# reloj6.net
KiCad netlist of a schematic drawn in EAGLE
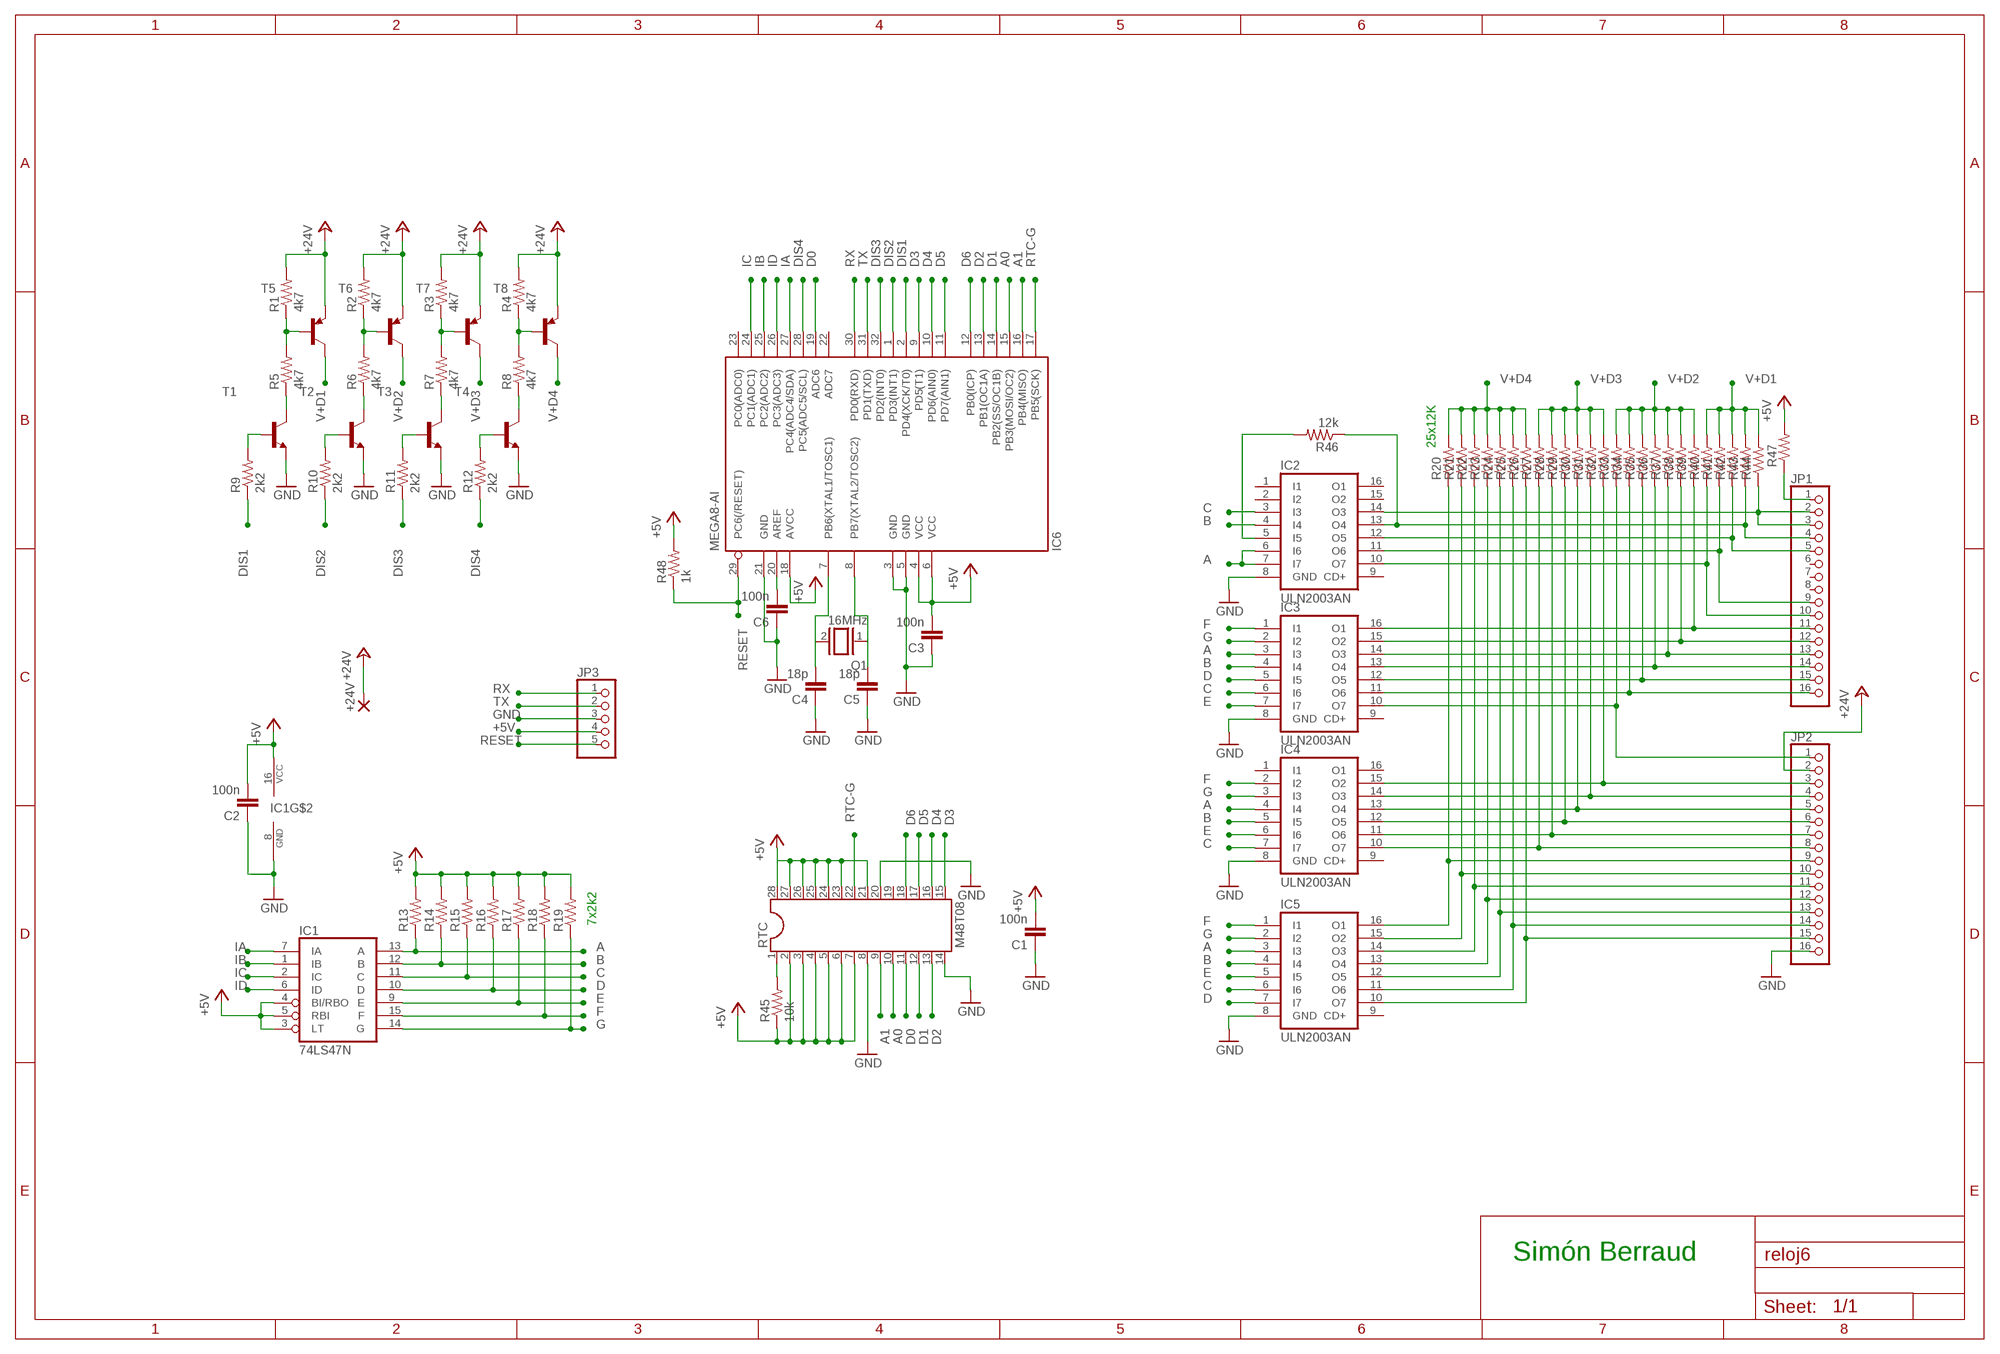
[diagram p0: schematic, sheet 1]

(export (version "E")
  (design (tool "Eeschema 10.0.6"))
  (components
    (comp (ref "+24V")
      (value "2,54/0,8")
      (footprint "eagle-import:2,54_0,8")
      (libsource (lib "eagle-import") (part "2,54/0,8"))
    )
    (comp (ref "C1")
      (value "100n")
      (footprint "eagle-import:C025-025X050")
      (libsource (lib "eagle-import") (part "C-EU025-025X050"))
    )
    (comp (ref "C2")
      (value "100n")
      (footprint "eagle-import:C025-025X050")
      (libsource (lib "eagle-import") (part "C-EU025-025X050"))
    )
    (comp (ref "C3")
      (value "100n")
      (footprint "eagle-import:C025-025X050")
      (libsource (lib "eagle-import") (part "C-EU025-025X050"))
    )
    (comp (ref "C4")
      (value "18p")
      (footprint "eagle-import:C0805K")
      (libsource (lib "eagle-import") (part "resistor_C-EUC0805K"))
    )
    (comp (ref "C5")
      (value "18p")
      (footprint "eagle-import:C0805K")
      (libsource (lib "eagle-import") (part "resistor_C-EUC0805K"))
    )
    (comp (ref "C6")
      (value "100n")
      (footprint "eagle-import:C0805K")
      (libsource (lib "eagle-import") (part "resistor_C-EUC0805K"))
    )
    (comp (ref "IC1")
      (value "74LS47N")
      (footprint "eagle-import:DIL16")
      (libsource (lib "eagle-import") (part "7447NLS"))
    )
    (comp (ref "IC2")
      (value "ULN2003AN")
      (footprint "eagle-import:DIL16")
      (libsource (lib "eagle-import") (part "ULN2003AN"))
    )
    (comp (ref "IC3")
      (value "ULN2003AN")
      (footprint "eagle-import:DIL16")
      (libsource (lib "eagle-import") (part "ULN2003AN"))
    )
    (comp (ref "IC4")
      (value "ULN2003AN")
      (footprint "eagle-import:DIL16")
      (libsource (lib "eagle-import") (part "ULN2003AN"))
    )
    (comp (ref "IC5")
      (value "ULN2003AN")
      (footprint "eagle-import:DIL16")
      (libsource (lib "eagle-import") (part "ULN2003AN"))
    )
    (comp (ref "IC6")
      (value "MEGA8-AI")
      (footprint "eagle-import:TQFP32-08")
      (fields (field (name "MPN") "ATMEGA8-16AU"))
      (libsource (lib "eagle-import") (part "MEGA8-AI"))
    )
    (comp (ref "JP1")
      (value "PINHD-1X16")
      (footprint "eagle-import:1X16")
      (libsource (lib "eagle-import") (part "PINHD-1X16"))
    )
    (comp (ref "JP2")
      (value "PINHD-1X16")
      (footprint "eagle-import:1X16")
      (libsource (lib "eagle-import") (part "PINHD-1X16"))
    )
    (comp (ref "JP3")
      (value "PINHD-1X5")
      (footprint "eagle-import:1X05")
      (libsource (lib "eagle-import") (part "PINHD-1X5"))
    )
    (comp (ref "Q1")
      (value "16MHz")
      (footprint "eagle-import:QS")
      (libsource (lib "eagle-import") (part "XTAL/S"))
    )
    (comp (ref "R1")
      (value "4k7")
      (footprint "eagle-import:0207_7")
      (libsource (lib "eagle-import") (part "R-US_0207/7"))
    )
    (comp (ref "R2")
      (value "4k7")
      (footprint "eagle-import:0207_7")
      (libsource (lib "eagle-import") (part "R-US_0207/7"))
    )
    (comp (ref "R3")
      (value "4k7")
      (footprint "eagle-import:0207_7")
      (libsource (lib "eagle-import") (part "R-US_0207/7"))
    )
    (comp (ref "R4")
      (value "4k7")
      (footprint "eagle-import:0207_7")
      (libsource (lib "eagle-import") (part "R-US_0207/7"))
    )
    (comp (ref "R5")
      (value "4k7")
      (footprint "eagle-import:0207_7")
      (libsource (lib "eagle-import") (part "R-US_0207/7"))
    )
    (comp (ref "R6")
      (value "4k7")
      (footprint "eagle-import:0207_7")
      (libsource (lib "eagle-import") (part "R-US_0207/7"))
    )
    (comp (ref "R7")
      (value "4k7")
      (footprint "eagle-import:0207_7")
      (libsource (lib "eagle-import") (part "R-US_0207/7"))
    )
    (comp (ref "R8")
      (value "4k7")
      (footprint "eagle-import:0207_7")
      (libsource (lib "eagle-import") (part "R-US_0207/7"))
    )
    (comp (ref "R9")
      (value "2k2")
      (footprint "eagle-import:0207_7")
      (libsource (lib "eagle-import") (part "R-US_0207/7"))
    )
    (comp (ref "R10")
      (value "2k2")
      (footprint "eagle-import:0207_7")
      (libsource (lib "eagle-import") (part "R-US_0207/7"))
    )
    (comp (ref "R11")
      (value "2k2")
      (footprint "eagle-import:0207_7")
      (libsource (lib "eagle-import") (part "R-US_0207/7"))
    )
    (comp (ref "R12")
      (value "2k2")
      (footprint "eagle-import:0207_7")
      (libsource (lib "eagle-import") (part "R-US_0207/7"))
    )
    (comp (ref "R13")
      (value "R-US_0207/7")
      (footprint "eagle-import:0207_7")
      (libsource (lib "eagle-import") (part "R-US_0207/7"))
    )
    (comp (ref "R14")
      (value "R-US_0207/7")
      (footprint "eagle-import:0207_7")
      (libsource (lib "eagle-import") (part "R-US_0207/7"))
    )
    (comp (ref "R15")
      (value "R-US_0207/7")
      (footprint "eagle-import:0207_7")
      (libsource (lib "eagle-import") (part "R-US_0207/7"))
    )
    (comp (ref "R16")
      (value "R-US_0207/7")
      (footprint "eagle-import:0207_7")
      (libsource (lib "eagle-import") (part "R-US_0207/7"))
    )
    (comp (ref "R17")
      (value "R-US_0207/7")
      (footprint "eagle-import:0207_7")
      (libsource (lib "eagle-import") (part "R-US_0207/7"))
    )
    (comp (ref "R18")
      (value "R-US_0207/7")
      (footprint "eagle-import:0207_7")
      (libsource (lib "eagle-import") (part "R-US_0207/7"))
    )
    (comp (ref "R19")
      (value "R-US_0207/7")
      (footprint "eagle-import:0207_7")
      (libsource (lib "eagle-import") (part "R-US_0207/7"))
    )
    (comp (ref "R20")
      (value "R-US_0207/7")
      (footprint "eagle-import:0207_7")
      (libsource (lib "eagle-import") (part "R-US_0207/7"))
    )
    (comp (ref "R21")
      (value "R-US_0207/7")
      (footprint "eagle-import:0207_7")
      (libsource (lib "eagle-import") (part "R-US_0207/7"))
    )
    (comp (ref "R22")
      (value "R-US_0207/7")
      (footprint "eagle-import:0207_7")
      (libsource (lib "eagle-import") (part "R-US_0207/7"))
    )
    (comp (ref "R23")
      (value "R-US_0207/7")
      (footprint "eagle-import:0207_7")
      (libsource (lib "eagle-import") (part "R-US_0207/7"))
    )
    (comp (ref "R24")
      (value "R-US_0207/7")
      (footprint "eagle-import:0207_7")
      (libsource (lib "eagle-import") (part "R-US_0207/7"))
    )
    (comp (ref "R25")
      (value "R-US_0207/7")
      (footprint "eagle-import:0207_7")
      (libsource (lib "eagle-import") (part "R-US_0207/7"))
    )
    (comp (ref "R26")
      (value "R-US_0207/7")
      (footprint "eagle-import:0207_7")
      (libsource (lib "eagle-import") (part "R-US_0207/7"))
    )
    (comp (ref "R27")
      (value "R-US_0207/7")
      (footprint "eagle-import:0207_7")
      (libsource (lib "eagle-import") (part "R-US_0207/7"))
    )
    (comp (ref "R28")
      (value "R-US_0207/7")
      (footprint "eagle-import:0207_7")
      (libsource (lib "eagle-import") (part "R-US_0207/7"))
    )
    (comp (ref "R29")
      (value "R-US_0207/7")
      (footprint "eagle-import:0207_7")
      (libsource (lib "eagle-import") (part "R-US_0207/7"))
    )
    (comp (ref "R30")
      (value "R-US_0207/7")
      (footprint "eagle-import:0207_7")
      (libsource (lib "eagle-import") (part "R-US_0207/7"))
    )
    (comp (ref "R31")
      (value "R-US_0207/7")
      (footprint "eagle-import:0207_7")
      (libsource (lib "eagle-import") (part "R-US_0207/7"))
    )
    (comp (ref "R32")
      (value "R-US_0207/7")
      (footprint "eagle-import:0207_7")
      (libsource (lib "eagle-import") (part "R-US_0207/7"))
    )
    (comp (ref "R33")
      (value "R-US_0207/7")
      (footprint "eagle-import:0207_7")
      (libsource (lib "eagle-import") (part "R-US_0207/7"))
    )
    (comp (ref "R34")
      (value "R-US_0207/7")
      (footprint "eagle-import:0207_7")
      (libsource (lib "eagle-import") (part "R-US_0207/7"))
    )
    (comp (ref "R35")
      (value "R-US_0207/7")
      (footprint "eagle-import:0207_7")
      (libsource (lib "eagle-import") (part "R-US_0207/7"))
    )
    (comp (ref "R36")
      (value "R-US_0207/7")
      (footprint "eagle-import:0207_7")
      (libsource (lib "eagle-import") (part "R-US_0207/7"))
    )
    (comp (ref "R37")
      (value "R-US_0207/7")
      (footprint "eagle-import:0207_7")
      (libsource (lib "eagle-import") (part "R-US_0207/7"))
    )
    (comp (ref "R38")
      (value "R-US_0207/7")
      (footprint "eagle-import:0207_7")
      (libsource (lib "eagle-import") (part "R-US_0207/7"))
    )
    (comp (ref "R39")
      (value "R-US_0207/7")
      (footprint "eagle-import:0207_7")
      (libsource (lib "eagle-import") (part "R-US_0207/7"))
    )
    (comp (ref "R40")
      (value "R-US_0207/7")
      (footprint "eagle-import:0207_7")
      (libsource (lib "eagle-import") (part "R-US_0207/7"))
    )
    (comp (ref "R41")
      (value "R-US_0207/7")
      (footprint "eagle-import:0207_7")
      (libsource (lib "eagle-import") (part "R-US_0207/7"))
    )
    (comp (ref "R42")
      (value "R-US_0207/7")
      (footprint "eagle-import:0207_7")
      (libsource (lib "eagle-import") (part "R-US_0207/7"))
    )
    (comp (ref "R43")
      (value "R-US_0207/7")
      (footprint "eagle-import:0207_7")
      (libsource (lib "eagle-import") (part "R-US_0207/7"))
    )
    (comp (ref "R44")
      (value "R-US_0207/7")
      (footprint "eagle-import:0207_7")
      (libsource (lib "eagle-import") (part "R-US_0207/7"))
    )
    (comp (ref "R45")
      (value "10k")
      (footprint "eagle-import:0207_7")
      (libsource (lib "eagle-import") (part "R-US_0207/7"))
    )
    (comp (ref "R46")
      (value "12k")
      (footprint "eagle-import:0207_7")
      (libsource (lib "eagle-import") (part "R-US_0207/7"))
    )
    (comp (ref "R47")
      (value "R-US_0411/12")
      (footprint "eagle-import:0411_12")
      (libsource (lib "eagle-import") (part "R-US_0411/12"))
    )
    (comp (ref "R48")
      (value "1k")
      (footprint "eagle-import:R1206")
      (libsource (lib "eagle-import") (part "R-US_R1206"))
    )
    (comp (ref "RTC")
      (value "M48T08")
      (footprint "eagle-import:DIL28-6")
      (libsource (lib "eagle-import") (part "DIL28"))
    )
    (comp (ref "T1")
      (value "BC169-NPN-TO92-ECB")
      (footprint "eagle-import:TO92-ECB")
      (libsource (lib "eagle-import") (part "-NPN-TO92-ECBBC169"))
    )
    (comp (ref "T2")
      (value "BC169-NPN-TO92-ECB")
      (footprint "eagle-import:TO92-ECB")
      (libsource (lib "eagle-import") (part "-NPN-TO92-ECBBC169"))
    )
    (comp (ref "T3")
      (value "BC169-NPN-TO92-ECB")
      (footprint "eagle-import:TO92-ECB")
      (libsource (lib "eagle-import") (part "-NPN-TO92-ECBBC169"))
    )
    (comp (ref "T4")
      (value "BC169-NPN-TO92-ECB")
      (footprint "eagle-import:TO92-ECB")
      (libsource (lib "eagle-import") (part "-NPN-TO92-ECBBC169"))
    )
    (comp (ref "T5")
      (value "-PNP-TO92-ECB")
      (footprint "eagle-import:TO92-ECB")
      (libsource (lib "eagle-import") (part "-PNP-TO92-ECB"))
    )
    (comp (ref "T6")
      (value "-PNP-TO92-ECB")
      (footprint "eagle-import:TO92-ECB")
      (libsource (lib "eagle-import") (part "-PNP-TO92-ECB"))
    )
    (comp (ref "T7")
      (value "-PNP-TO92-ECB")
      (footprint "eagle-import:TO92-ECB")
      (libsource (lib "eagle-import") (part "-PNP-TO92-ECB"))
    )
    (comp (ref "T8")
      (value "-PNP-TO92-ECB")
      (footprint "eagle-import:TO92-ECB")
      (libsource (lib "eagle-import") (part "-PNP-TO92-ECB"))
    )
  )
  (nets
    (net (code "1") (name "+5V") (class "Default")
      (node (ref "C1") (pin "2") (pinfunction "2_2") (pintype "passive"))
      (node (ref "C2") (pin "2") (pinfunction "2_2") (pintype "passive"))
      (node (ref "C3") (pin "2") (pinfunction "2_2") (pintype "passive"))
      (node (ref "IC1") (pin "16") (pinfunction "VCC_16") (pintype "power_in"))
      (node (ref "IC1") (pin "3") (pinfunction "LT_3") (pintype "input"))
      (node (ref "IC1") (pin "4") (pinfunction "BI/RBO_4") (pintype "input"))
      (node (ref "IC1") (pin "5") (pinfunction "RBI_5") (pintype "input"))
      (node (ref "IC6") (pin "18") (pinfunction "AVCC_18") (pintype "power_in"))
      (node (ref "IC6") (pin "4") (pinfunction "VCC_4") (pintype "power_in"))
      (node (ref "IC6") (pin "6") (pinfunction "VCC_6") (pintype "power_in"))
      (node (ref "JP3") (pin "4") (pinfunction "4_4") (pintype "passive"))
      (node (ref "R13") (pin "2") (pinfunction "2_2") (pintype "passive"))
      (node (ref "R14") (pin "2") (pinfunction "2_2") (pintype "passive"))
      (node (ref "R15") (pin "2") (pinfunction "2_2") (pintype "passive"))
      (node (ref "R16") (pin "2") (pinfunction "2_2") (pintype "passive"))
      (node (ref "R17") (pin "2") (pinfunction "2_2") (pintype "passive"))
      (node (ref "R18") (pin "2") (pinfunction "2_2") (pintype "passive"))
      (node (ref "R19") (pin "2") (pinfunction "2_2") (pintype "passive"))
      (node (ref "R45") (pin "1") (pinfunction "1_1") (pintype "passive"))
      (node (ref "R47") (pin "2") (pinfunction "2_2") (pintype "passive"))
      (node (ref "R48") (pin "2") (pinfunction "2_2") (pintype "passive"))
      (node (ref "RTC") (pin "2") (pinfunction "2_2") (pintype "passive"))
      (node (ref "RTC") (pin "21") (pinfunction "21_21") (pintype "passive"))
      (node (ref "RTC") (pin "23") (pinfunction "23_23") (pintype "passive"))
      (node (ref "RTC") (pin "24") (pinfunction "24_24") (pintype "passive"))
      (node (ref "RTC") (pin "25") (pinfunction "25_25") (pintype "passive"))
      (node (ref "RTC") (pin "26") (pinfunction "26_26") (pintype "passive"))
      (node (ref "RTC") (pin "27") (pinfunction "27_27") (pintype "passive"))
      (node (ref "RTC") (pin "28") (pinfunction "28_28") (pintype "passive"))
      (node (ref "RTC") (pin "3") (pinfunction "3_3") (pintype "passive"))
      (node (ref "RTC") (pin "4") (pinfunction "4_4") (pintype "passive"))
      (node (ref "RTC") (pin "5") (pinfunction "5_5") (pintype "passive"))
      (node (ref "RTC") (pin "6") (pinfunction "6_6") (pintype "passive"))
      (node (ref "RTC") (pin "7") (pinfunction "7_7") (pintype "passive"))
    )
    (net (code "2") (name "+24V") (class "Default")
      (node (ref "+24V") (pin "1") (pinfunction "P_1") (pintype "passive"))
      (node (ref "JP2") (pin "2") (pinfunction "2_2") (pintype "passive"))
      (node (ref "R1") (pin "2") (pinfunction "2_2") (pintype "passive"))
      (node (ref "R2") (pin "2") (pinfunction "2_2") (pintype "passive"))
      (node (ref "R3") (pin "2") (pinfunction "2_2") (pintype "passive"))
      (node (ref "R4") (pin "2") (pinfunction "2_2") (pintype "passive"))
      (node (ref "T5") (pin "E") (pinfunction "E_E") (pintype "passive"))
      (node (ref "T6") (pin "E") (pinfunction "E_E") (pintype "passive"))
      (node (ref "T7") (pin "E") (pinfunction "E_E") (pintype "passive"))
      (node (ref "T8") (pin "E") (pinfunction "E_E") (pintype "passive"))
    )
    (net (code "3") (name "/A") (class "Default")
      (node (ref "IC1") (pin "13") (pinfunction "A_13") (pintype "output"))
      (node (ref "IC2") (pin "6") (pinfunction "I6_6") (pintype "input"))
      (node (ref "IC2") (pin "7") (pinfunction "I7_7") (pintype "input"))
      (node (ref "IC3") (pin "3") (pinfunction "I3_3") (pintype "input"))
      (node (ref "IC4") (pin "4") (pinfunction "I4_4") (pintype "input"))
      (node (ref "IC5") (pin "3") (pinfunction "I3_3") (pintype "input"))
      (node (ref "R13") (pin "1") (pinfunction "1_1") (pintype "passive"))
    )
    (net (code "4") (name "/A0") (class "Default")
      (node (ref "IC6") (pin "15") (pinfunction "PB3(MOSI/OC2)_15") (pintype "bidirectional"))
      (node (ref "RTC") (pin "10") (pinfunction "10_10") (pintype "passive"))
    )
    (net (code "5") (name "/A1") (class "Default")
      (node (ref "IC6") (pin "16") (pinfunction "PB4(MISO)_16") (pintype "bidirectional"))
      (node (ref "RTC") (pin "9") (pinfunction "9_9") (pintype "passive"))
    )
    (net (code "6") (name "/B") (class "Default")
      (node (ref "IC1") (pin "12") (pinfunction "B_12") (pintype "output"))
      (node (ref "IC2") (pin "4") (pinfunction "I4_4") (pintype "input"))
      (node (ref "IC3") (pin "4") (pinfunction "I4_4") (pintype "input"))
      (node (ref "IC4") (pin "5") (pinfunction "I5_5") (pintype "input"))
      (node (ref "IC5") (pin "4") (pinfunction "I4_4") (pintype "input"))
      (node (ref "R14") (pin "1") (pinfunction "1_1") (pintype "passive"))
    )
    (net (code "7") (name "/C") (class "Default")
      (node (ref "IC1") (pin "11") (pinfunction "C_11") (pintype "output"))
      (node (ref "IC2") (pin "3") (pinfunction "I3_3") (pintype "input"))
      (node (ref "IC3") (pin "6") (pinfunction "I6_6") (pintype "input"))
      (node (ref "IC4") (pin "7") (pinfunction "I7_7") (pintype "input"))
      (node (ref "IC5") (pin "6") (pinfunction "I6_6") (pintype "input"))
      (node (ref "R15") (pin "1") (pinfunction "1_1") (pintype "passive"))
    )
    (net (code "8") (name "/D") (class "Default")
      (node (ref "IC1") (pin "10") (pinfunction "D_10") (pintype "output"))
      (node (ref "IC3") (pin "5") (pinfunction "I5_5") (pintype "input"))
      (node (ref "IC5") (pin "7") (pinfunction "I7_7") (pintype "input"))
      (node (ref "R16") (pin "1") (pinfunction "1_1") (pintype "passive"))
    )
    (net (code "9") (name "/D0") (class "Default")
      (node (ref "IC6") (pin "19") (pinfunction "ADC6_19") (pintype "bidirectional"))
      (node (ref "RTC") (pin "11") (pinfunction "11_11") (pintype "passive"))
    )
    (net (code "10") (name "/D1") (class "Default")
      (node (ref "IC6") (pin "14") (pinfunction "PB2(SS/OC1B)_14") (pintype "bidirectional"))
      (node (ref "RTC") (pin "12") (pinfunction "12_12") (pintype "passive"))
    )
    (net (code "11") (name "/D2") (class "Default")
      (node (ref "IC6") (pin "13") (pinfunction "PB1(OC1A)_13") (pintype "bidirectional"))
      (node (ref "RTC") (pin "13") (pinfunction "13_13") (pintype "passive"))
    )
    (net (code "12") (name "/D3") (class "Default")
      (node (ref "IC6") (pin "9") (pinfunction "PD5(T1)_9") (pintype "bidirectional"))
      (node (ref "RTC") (pin "15") (pinfunction "15_15") (pintype "passive"))
    )
    (net (code "13") (name "/D4") (class "Default")
      (node (ref "IC6") (pin "10") (pinfunction "PD6(AIN0)_10") (pintype "bidirectional"))
      (node (ref "RTC") (pin "16") (pinfunction "16_16") (pintype "passive"))
    )
    (net (code "14") (name "/D5") (class "Default")
      (node (ref "IC6") (pin "11") (pinfunction "PD7(AIN1)_11") (pintype "bidirectional"))
      (node (ref "RTC") (pin "17") (pinfunction "17_17") (pintype "passive"))
    )
    (net (code "15") (name "/D6") (class "Default")
      (node (ref "IC6") (pin "12") (pinfunction "PB0(ICP)_12") (pintype "bidirectional"))
      (node (ref "RTC") (pin "18") (pinfunction "18_18") (pintype "passive"))
    )
    (net (code "16") (name "/DIS1") (class "Default")
      (node (ref "IC6") (pin "2") (pinfunction "PD4(XCK/T0)_2") (pintype "bidirectional"))
      (node (ref "R9") (pin "1") (pinfunction "1_1") (pintype "passive"))
    )
    (net (code "17") (name "/DIS2") (class "Default")
      (node (ref "IC6") (pin "1") (pinfunction "PD3(INT1)_1") (pintype "bidirectional"))
      (node (ref "R10") (pin "1") (pinfunction "1_1") (pintype "passive"))
    )
    (net (code "18") (name "/DIS3") (class "Default")
      (node (ref "IC6") (pin "32") (pinfunction "PD2(INT0)_32") (pintype "bidirectional"))
      (node (ref "R11") (pin "1") (pinfunction "1_1") (pintype "passive"))
    )
    (net (code "19") (name "/DIS4") (class "Default")
      (node (ref "IC6") (pin "28") (pinfunction "PC5(ADC5/SCL)_28") (pintype "bidirectional"))
      (node (ref "R12") (pin "1") (pinfunction "1_1") (pintype "passive"))
    )
    (net (code "20") (name "/E") (class "Default")
      (node (ref "IC1") (pin "9") (pinfunction "E_9") (pintype "output"))
      (node (ref "IC3") (pin "7") (pinfunction "I7_7") (pintype "input"))
      (node (ref "IC4") (pin "6") (pinfunction "I6_6") (pintype "input"))
      (node (ref "IC5") (pin "5") (pinfunction "I5_5") (pintype "input"))
      (node (ref "R17") (pin "1") (pinfunction "1_1") (pintype "passive"))
    )
    (net (code "21") (name "/F") (class "Default")
      (node (ref "IC1") (pin "15") (pinfunction "F_15") (pintype "output"))
      (node (ref "IC3") (pin "1") (pinfunction "I1_1") (pintype "input"))
      (node (ref "IC4") (pin "2") (pinfunction "I2_2") (pintype "input"))
      (node (ref "IC5") (pin "1") (pinfunction "I1_1") (pintype "input"))
      (node (ref "R18") (pin "1") (pinfunction "1_1") (pintype "passive"))
    )
    (net (code "22") (name "/G") (class "Default")
      (node (ref "IC1") (pin "14") (pinfunction "G_14") (pintype "output"))
      (node (ref "IC3") (pin "2") (pinfunction "I2_2") (pintype "input"))
      (node (ref "IC4") (pin "3") (pinfunction "I3_3") (pintype "input"))
      (node (ref "IC5") (pin "2") (pinfunction "I2_2") (pintype "input"))
      (node (ref "R19") (pin "1") (pinfunction "1_1") (pintype "passive"))
    )
    (net (code "23") (name "/IA") (class "Default")
      (node (ref "IC1") (pin "7") (pinfunction "IA_7") (pintype "input"))
      (node (ref "IC6") (pin "27") (pinfunction "PC4(ADC4/SDA)_27") (pintype "bidirectional"))
    )
    (net (code "24") (name "/IB") (class "Default")
      (node (ref "IC1") (pin "1") (pinfunction "IB_1") (pintype "input"))
      (node (ref "IC6") (pin "25") (pinfunction "PC2(ADC2)_25") (pintype "bidirectional"))
    )
    (net (code "25") (name "/IC") (class "Default")
      (node (ref "IC1") (pin "2") (pinfunction "IC_2") (pintype "input"))
      (node (ref "IC6") (pin "24") (pinfunction "PC1(ADC1)_24") (pintype "bidirectional"))
    )
    (net (code "26") (name "/ID") (class "Default")
      (node (ref "IC1") (pin "6") (pinfunction "ID_6") (pintype "input"))
      (node (ref "IC6") (pin "26") (pinfunction "PC3(ADC3)_26") (pintype "bidirectional"))
    )
    (net (code "27") (name "/RESET") (class "Default")
      (node (ref "IC6") (pin "29") (pinfunction "PC6(/RESET)_29") (pintype "bidirectional"))
      (node (ref "JP3") (pin "5") (pinfunction "5_5") (pintype "passive"))
      (node (ref "R48") (pin "1") (pinfunction "1_1") (pintype "passive"))
    )
    (net (code "28") (name "/RTC-G") (class "Default")
      (node (ref "IC6") (pin "17") (pinfunction "PB5(SCK)_17") (pintype "bidirectional"))
      (node (ref "RTC") (pin "22") (pinfunction "22_22") (pintype "passive"))
    )
    (net (code "29") (name "/RX") (class "Default")
      (node (ref "IC6") (pin "30") (pinfunction "PD0(RXD)_30") (pintype "bidirectional"))
      (node (ref "JP3") (pin "1") (pinfunction "1_1") (pintype "passive"))
    )
    (net (code "30") (name "/TX") (class "Default")
      (node (ref "IC6") (pin "31") (pinfunction "PD1(TXD)_31") (pintype "bidirectional"))
      (node (ref "JP3") (pin "2") (pinfunction "2_2") (pintype "passive"))
    )
    (net (code "31") (name "/V+D1") (class "Default")
      (node (ref "R40") (pin "2") (pinfunction "2_2") (pintype "passive"))
      (node (ref "R41") (pin "2") (pinfunction "2_2") (pintype "passive"))
      (node (ref "R42") (pin "2") (pinfunction "2_2") (pintype "passive"))
      (node (ref "R43") (pin "2") (pinfunction "2_2") (pintype "passive"))
      (node (ref "R44") (pin "2") (pinfunction "2_2") (pintype "passive"))
      (node (ref "T5") (pin "C") (pinfunction "C_C") (pintype "passive"))
    )
    (net (code "32") (name "/V+D2") (class "Default")
      (node (ref "R33") (pin "2") (pinfunction "2_2") (pintype "passive"))
      (node (ref "R34") (pin "2") (pinfunction "2_2") (pintype "passive"))
      (node (ref "R35") (pin "2") (pinfunction "2_2") (pintype "passive"))
      (node (ref "R36") (pin "2") (pinfunction "2_2") (pintype "passive"))
      (node (ref "R37") (pin "2") (pinfunction "2_2") (pintype "passive"))
      (node (ref "R38") (pin "2") (pinfunction "2_2") (pintype "passive"))
      (node (ref "R39") (pin "2") (pinfunction "2_2") (pintype "passive"))
      (node (ref "T6") (pin "C") (pinfunction "C_C") (pintype "passive"))
    )
    (net (code "33") (name "/V+D3") (class "Default")
      (node (ref "R27") (pin "2") (pinfunction "2_2") (pintype "passive"))
      (node (ref "R28") (pin "2") (pinfunction "2_2") (pintype "passive"))
      (node (ref "R29") (pin "2") (pinfunction "2_2") (pintype "passive"))
      (node (ref "R30") (pin "2") (pinfunction "2_2") (pintype "passive"))
      (node (ref "R31") (pin "2") (pinfunction "2_2") (pintype "passive"))
      (node (ref "R32") (pin "2") (pinfunction "2_2") (pintype "passive"))
      (node (ref "T7") (pin "C") (pinfunction "C_C") (pintype "passive"))
    )
    (net (code "34") (name "/V+D4") (class "Default")
      (node (ref "R20") (pin "2") (pinfunction "2_2") (pintype "passive"))
      (node (ref "R21") (pin "2") (pinfunction "2_2") (pintype "passive"))
      (node (ref "R22") (pin "2") (pinfunction "2_2") (pintype "passive"))
      (node (ref "R23") (pin "2") (pinfunction "2_2") (pintype "passive"))
      (node (ref "R24") (pin "2") (pinfunction "2_2") (pintype "passive"))
      (node (ref "R25") (pin "2") (pinfunction "2_2") (pintype "passive"))
      (node (ref "R26") (pin "2") (pinfunction "2_2") (pintype "passive"))
      (node (ref "T8") (pin "C") (pinfunction "C_C") (pintype "passive"))
    )
    (net (code "35") (name "GND") (class "Default")
      (node (ref "C1") (pin "1") (pinfunction "1_1") (pintype "passive"))
      (node (ref "C2") (pin "1") (pinfunction "1_1") (pintype "passive"))
      (node (ref "C3") (pin "1") (pinfunction "1_1") (pintype "passive"))
      (node (ref "C4") (pin "1") (pinfunction "1_1") (pintype "passive"))
      (node (ref "C5") (pin "1") (pinfunction "1_1") (pintype "passive"))
      (node (ref "C6") (pin "1") (pinfunction "1_1") (pintype "passive"))
      (node (ref "IC1") (pin "8") (pinfunction "GND_8") (pintype "power_in"))
      (node (ref "IC2") (pin "8") (pinfunction "GND_8") (pintype "power_in"))
      (node (ref "IC3") (pin "8") (pinfunction "GND_8") (pintype "power_in"))
      (node (ref "IC4") (pin "8") (pinfunction "GND_8") (pintype "power_in"))
      (node (ref "IC5") (pin "8") (pinfunction "GND_8") (pintype "power_in"))
      (node (ref "IC6") (pin "21") (pinfunction "GND_21") (pintype "power_in"))
      (node (ref "IC6") (pin "3") (pinfunction "GND_3") (pintype "power_in"))
      (node (ref "IC6") (pin "5") (pinfunction "GND_5") (pintype "power_in"))
      (node (ref "JP2") (pin "16") (pinfunction "16_16") (pintype "passive"))
      (node (ref "JP3") (pin "3") (pinfunction "3_3") (pintype "passive"))
      (node (ref "RTC") (pin "14") (pinfunction "14_14") (pintype "passive"))
      (node (ref "RTC") (pin "20") (pinfunction "20_20") (pintype "passive"))
      (node (ref "RTC") (pin "8") (pinfunction "8_8") (pintype "passive"))
      (node (ref "T1") (pin "E") (pinfunction "E_E") (pintype "passive"))
      (node (ref "T2") (pin "E") (pinfunction "E_E") (pintype "passive"))
      (node (ref "T3") (pin "E") (pinfunction "E_E") (pintype "passive"))
      (node (ref "T4") (pin "E") (pinfunction "E_E") (pintype "passive"))
    )
    (net (code "36") (name "Net-(IC2-I5)") (class "Default")
      (node (ref "IC2") (pin "5") (pinfunction "I5_5") (pintype "input"))
      (node (ref "R46") (pin "2") (pinfunction "2_2") (pintype "passive"))
    )
    (net (code "37") (name "Net-(IC2-O3)") (class "Default")
      (node (ref "IC2") (pin "14") (pinfunction "O3_14") (pintype "open_collector"))
      (node (ref "JP1") (pin "2") (pinfunction "2_2") (pintype "passive"))
      (node (ref "JP1") (pin "3") (pinfunction "3_3") (pintype "passive"))
      (node (ref "R44") (pin "1") (pinfunction "1_1") (pintype "passive"))
    )
    (net (code "38") (name "Net-(IC2-O4)") (class "Default")
      (node (ref "IC2") (pin "13") (pinfunction "O4_13") (pintype "open_collector"))
      (node (ref "JP1") (pin "4") (pinfunction "4_4") (pintype "passive"))
      (node (ref "R43") (pin "1") (pinfunction "1_1") (pintype "passive"))
      (node (ref "R46") (pin "1") (pinfunction "1_1") (pintype "passive"))
    )
    (net (code "39") (name "Net-(IC2-O5)") (class "Default")
      (node (ref "IC2") (pin "12") (pinfunction "O5_12") (pintype "open_collector"))
      (node (ref "JP1") (pin "5") (pinfunction "5_5") (pintype "passive"))
      (node (ref "R42") (pin "1") (pinfunction "1_1") (pintype "passive"))
    )
    (net (code "40") (name "Net-(IC2-O6)") (class "Default")
      (node (ref "IC2") (pin "11") (pinfunction "O6_11") (pintype "open_collector"))
      (node (ref "JP1") (pin "9") (pinfunction "9_9") (pintype "passive"))
      (node (ref "R41") (pin "1") (pinfunction "1_1") (pintype "passive"))
    )
    (net (code "41") (name "Net-(IC2-O7)") (class "Default")
      (node (ref "IC2") (pin "10") (pinfunction "O7_10") (pintype "open_collector"))
      (node (ref "JP1") (pin "10") (pinfunction "10_10") (pintype "passive"))
      (node (ref "R40") (pin "1") (pinfunction "1_1") (pintype "passive"))
    )
    (net (code "42") (name "Net-(IC3-O1)") (class "Default")
      (node (ref "IC3") (pin "16") (pinfunction "O1_16") (pintype "open_collector"))
      (node (ref "JP1") (pin "11") (pinfunction "11_11") (pintype "passive"))
      (node (ref "R39") (pin "1") (pinfunction "1_1") (pintype "passive"))
    )
    (net (code "43") (name "Net-(IC3-O2)") (class "Default")
      (node (ref "IC3") (pin "15") (pinfunction "O2_15") (pintype "open_collector"))
      (node (ref "JP1") (pin "12") (pinfunction "12_12") (pintype "passive"))
      (node (ref "R38") (pin "1") (pinfunction "1_1") (pintype "passive"))
    )
    (net (code "44") (name "Net-(IC3-O3)") (class "Default")
      (node (ref "IC3") (pin "14") (pinfunction "O3_14") (pintype "open_collector"))
      (node (ref "JP1") (pin "13") (pinfunction "13_13") (pintype "passive"))
      (node (ref "R37") (pin "1") (pinfunction "1_1") (pintype "passive"))
    )
    (net (code "45") (name "Net-(IC3-O4)") (class "Default")
      (node (ref "IC3") (pin "13") (pinfunction "O4_13") (pintype "open_collector"))
      (node (ref "JP1") (pin "14") (pinfunction "14_14") (pintype "passive"))
      (node (ref "R36") (pin "1") (pinfunction "1_1") (pintype "passive"))
    )
    (net (code "46") (name "Net-(IC3-O5)") (class "Default")
      (node (ref "IC3") (pin "12") (pinfunction "O5_12") (pintype "open_collector"))
      (node (ref "JP1") (pin "15") (pinfunction "15_15") (pintype "passive"))
      (node (ref "R35") (pin "1") (pinfunction "1_1") (pintype "passive"))
    )
    (net (code "47") (name "Net-(IC3-O6)") (class "Default")
      (node (ref "IC3") (pin "11") (pinfunction "O6_11") (pintype "open_collector"))
      (node (ref "JP1") (pin "16") (pinfunction "16_16") (pintype "passive"))
      (node (ref "R34") (pin "1") (pinfunction "1_1") (pintype "passive"))
    )
    (net (code "48") (name "Net-(IC3-O7)") (class "Default")
      (node (ref "IC3") (pin "10") (pinfunction "O7_10") (pintype "open_collector"))
      (node (ref "JP2") (pin "1") (pinfunction "1_1") (pintype "passive"))
      (node (ref "R33") (pin "1") (pinfunction "1_1") (pintype "passive"))
    )
    (net (code "49") (name "Net-(IC4-O2)") (class "Default")
      (node (ref "IC4") (pin "15") (pinfunction "O2_15") (pintype "open_collector"))
      (node (ref "JP2") (pin "3") (pinfunction "3_3") (pintype "passive"))
      (node (ref "R32") (pin "1") (pinfunction "1_1") (pintype "passive"))
    )
    (net (code "50") (name "Net-(IC4-O3)") (class "Default")
      (node (ref "IC4") (pin "14") (pinfunction "O3_14") (pintype "open_collector"))
      (node (ref "JP2") (pin "4") (pinfunction "4_4") (pintype "passive"))
      (node (ref "R31") (pin "1") (pinfunction "1_1") (pintype "passive"))
    )
    (net (code "51") (name "Net-(IC4-O4)") (class "Default")
      (node (ref "IC4") (pin "13") (pinfunction "O4_13") (pintype "open_collector"))
      (node (ref "JP2") (pin "5") (pinfunction "5_5") (pintype "passive"))
      (node (ref "R30") (pin "1") (pinfunction "1_1") (pintype "passive"))
    )
    (net (code "52") (name "Net-(IC4-O5)") (class "Default")
      (node (ref "IC4") (pin "12") (pinfunction "O5_12") (pintype "open_collector"))
      (node (ref "JP2") (pin "6") (pinfunction "6_6") (pintype "passive"))
      (node (ref "R29") (pin "1") (pinfunction "1_1") (pintype "passive"))
    )
    (net (code "53") (name "Net-(IC4-O6)") (class "Default")
      (node (ref "IC4") (pin "11") (pinfunction "O6_11") (pintype "open_collector"))
      (node (ref "JP2") (pin "7") (pinfunction "7_7") (pintype "passive"))
      (node (ref "R28") (pin "1") (pinfunction "1_1") (pintype "passive"))
    )
    (net (code "54") (name "Net-(IC4-O7)") (class "Default")
      (node (ref "IC4") (pin "10") (pinfunction "O7_10") (pintype "open_collector"))
      (node (ref "JP2") (pin "8") (pinfunction "8_8") (pintype "passive"))
      (node (ref "R27") (pin "1") (pinfunction "1_1") (pintype "passive"))
    )
    (net (code "55") (name "Net-(IC5-O1)") (class "Default")
      (node (ref "IC5") (pin "16") (pinfunction "O1_16") (pintype "open_collector"))
      (node (ref "JP2") (pin "9") (pinfunction "9_9") (pintype "passive"))
      (node (ref "R20") (pin "1") (pinfunction "1_1") (pintype "passive"))
    )
    (net (code "56") (name "Net-(IC5-O2)") (class "Default")
      (node (ref "IC5") (pin "15") (pinfunction "O2_15") (pintype "open_collector"))
      (node (ref "JP2") (pin "10") (pinfunction "10_10") (pintype "passive"))
      (node (ref "R21") (pin "1") (pinfunction "1_1") (pintype "passive"))
    )
    (net (code "57") (name "Net-(IC5-O3)") (class "Default")
      (node (ref "IC5") (pin "14") (pinfunction "O3_14") (pintype "open_collector"))
      (node (ref "JP2") (pin "11") (pinfunction "11_11") (pintype "passive"))
      (node (ref "R22") (pin "1") (pinfunction "1_1") (pintype "passive"))
    )
    (net (code "58") (name "Net-(IC5-O4)") (class "Default")
      (node (ref "IC5") (pin "13") (pinfunction "O4_13") (pintype "open_collector"))
      (node (ref "JP2") (pin "12") (pinfunction "12_12") (pintype "passive"))
      (node (ref "R23") (pin "1") (pinfunction "1_1") (pintype "passive"))
    )
    (net (code "59") (name "Net-(IC5-O5)") (class "Default")
      (node (ref "IC5") (pin "12") (pinfunction "O5_12") (pintype "open_collector"))
      (node (ref "JP2") (pin "13") (pinfunction "13_13") (pintype "passive"))
      (node (ref "R24") (pin "1") (pinfunction "1_1") (pintype "passive"))
    )
    (net (code "60") (name "Net-(IC5-O6)") (class "Default")
      (node (ref "IC5") (pin "11") (pinfunction "O6_11") (pintype "open_collector"))
      (node (ref "JP2") (pin "14") (pinfunction "14_14") (pintype "passive"))
      (node (ref "R25") (pin "1") (pinfunction "1_1") (pintype "passive"))
    )
    (net (code "61") (name "Net-(IC5-O7)") (class "Default")
      (node (ref "IC5") (pin "10") (pinfunction "O7_10") (pintype "open_collector"))
      (node (ref "JP2") (pin "15") (pinfunction "15_15") (pintype "passive"))
      (node (ref "R26") (pin "1") (pinfunction "1_1") (pintype "passive"))
    )
    (net (code "62") (name "Net-(IC6-AREF)") (class "Default")
      (node (ref "C6") (pin "2") (pinfunction "2_2") (pintype "passive"))
      (node (ref "IC6") (pin "20") (pinfunction "AREF_20") (pintype "passive"))
    )
    (net (code "63") (name "Net-(IC6-PB6(XTAL1{slash}TOSC1))") (class "Default")
      (node (ref "C4") (pin "2") (pinfunction "2_2") (pintype "passive"))
      (node (ref "IC6") (pin "7") (pinfunction "PB6(XTAL1/TOSC1)_7") (pintype "bidirectional"))
      (node (ref "Q1") (pin "2") (pinfunction "2_2") (pintype "passive"))
    )
    (net (code "64") (name "Net-(IC6-PB7(XTAL2{slash}TOSC2))") (class "Default")
      (node (ref "C5") (pin "2") (pinfunction "2_2") (pintype "passive"))
      (node (ref "IC6") (pin "8") (pinfunction "PB7(XTAL2/TOSC2)_8") (pintype "bidirectional"))
      (node (ref "Q1") (pin "1") (pinfunction "1_1") (pintype "passive"))
    )
    (net (code "65") (name "Net-(JP1-Pad1)") (class "Default")
      (node (ref "JP1") (pin "1") (pinfunction "1_1") (pintype "passive"))
      (node (ref "R47") (pin "1") (pinfunction "1_1") (pintype "passive"))
    )
    (net (code "66") (name "Net-(R1-Pad1)") (class "Default")
      (node (ref "R1") (pin "1") (pinfunction "1_1") (pintype "passive"))
      (node (ref "R5") (pin "2") (pinfunction "2_2") (pintype "passive"))
      (node (ref "T5") (pin "B") (pinfunction "B_B") (pintype "passive"))
    )
    (net (code "67") (name "Net-(R2-Pad1)") (class "Default")
      (node (ref "R2") (pin "1") (pinfunction "1_1") (pintype "passive"))
      (node (ref "R6") (pin "2") (pinfunction "2_2") (pintype "passive"))
      (node (ref "T6") (pin "B") (pinfunction "B_B") (pintype "passive"))
    )
    (net (code "68") (name "Net-(R3-Pad1)") (class "Default")
      (node (ref "R3") (pin "1") (pinfunction "1_1") (pintype "passive"))
      (node (ref "R7") (pin "2") (pinfunction "2_2") (pintype "passive"))
      (node (ref "T7") (pin "B") (pinfunction "B_B") (pintype "passive"))
    )
    (net (code "69") (name "Net-(R4-Pad1)") (class "Default")
      (node (ref "R4") (pin "1") (pinfunction "1_1") (pintype "passive"))
      (node (ref "R8") (pin "2") (pinfunction "2_2") (pintype "passive"))
      (node (ref "T8") (pin "B") (pinfunction "B_B") (pintype "passive"))
    )
    (net (code "70") (name "Net-(R5-Pad1)") (class "Default")
      (node (ref "R5") (pin "1") (pinfunction "1_1") (pintype "passive"))
      (node (ref "T1") (pin "C") (pinfunction "C_C") (pintype "passive"))
    )
    (net (code "71") (name "Net-(R6-Pad1)") (class "Default")
      (node (ref "R6") (pin "1") (pinfunction "1_1") (pintype "passive"))
      (node (ref "T2") (pin "C") (pinfunction "C_C") (pintype "passive"))
    )
    (net (code "72") (name "Net-(R7-Pad1)") (class "Default")
      (node (ref "R7") (pin "1") (pinfunction "1_1") (pintype "passive"))
      (node (ref "T3") (pin "C") (pinfunction "C_C") (pintype "passive"))
    )
    (net (code "73") (name "Net-(R8-Pad1)") (class "Default")
      (node (ref "R8") (pin "1") (pinfunction "1_1") (pintype "passive"))
      (node (ref "T4") (pin "C") (pinfunction "C_C") (pintype "passive"))
    )
    (net (code "74") (name "Net-(R9-Pad2)") (class "Default")
      (node (ref "R9") (pin "2") (pinfunction "2_2") (pintype "passive"))
      (node (ref "T1") (pin "B") (pinfunction "B_B") (pintype "passive"))
    )
    (net (code "75") (name "Net-(R10-Pad2)") (class "Default")
      (node (ref "R10") (pin "2") (pinfunction "2_2") (pintype "passive"))
      (node (ref "T2") (pin "B") (pinfunction "B_B") (pintype "passive"))
    )
    (net (code "76") (name "Net-(R11-Pad2)") (class "Default")
      (node (ref "R11") (pin "2") (pinfunction "2_2") (pintype "passive"))
      (node (ref "T3") (pin "B") (pinfunction "B_B") (pintype "passive"))
    )
    (net (code "77") (name "Net-(R12-Pad2)") (class "Default")
      (node (ref "R12") (pin "2") (pinfunction "2_2") (pintype "passive"))
      (node (ref "T4") (pin "B") (pinfunction "B_B") (pintype "passive"))
    )
    (net (code "78") (name "Net-(R45-Pad2)") (class "Default")
      (node (ref "R45") (pin "2") (pinfunction "2_2") (pintype "passive"))
      (node (ref "RTC") (pin "1") (pinfunction "1_1") (pintype "passive"))
    )
    (net (code "79") (name "unconnected-(IC2-CD+-Pad9)") (class "Default")
      (node (ref "IC2") (pin "9") (pinfunction "CD+_9") (pintype "passive"))
    )
    (net (code "80") (name "unconnected-(IC2-I1-Pad1)") (class "Default")
      (node (ref "IC2") (pin "1") (pinfunction "I1_1") (pintype "input"))
    )
    (net (code "81") (name "unconnected-(IC2-I2-Pad2)") (class "Default")
      (node (ref "IC2") (pin "2") (pinfunction "I2_2") (pintype "input"))
    )
    (net (code "82") (name "unconnected-(IC2-O1-Pad16)") (class "Default")
      (node (ref "IC2") (pin "16") (pinfunction "O1_16") (pintype "open_collector"))
    )
    (net (code "83") (name "unconnected-(IC2-O2-Pad15)") (class "Default")
      (node (ref "IC2") (pin "15") (pinfunction "O2_15") (pintype "open_collector"))
    )
    (net (code "84") (name "unconnected-(IC3-CD+-Pad9)") (class "Default")
      (node (ref "IC3") (pin "9") (pinfunction "CD+_9") (pintype "passive"))
    )
    (net (code "85") (name "unconnected-(IC4-CD+-Pad9)") (class "Default")
      (node (ref "IC4") (pin "9") (pinfunction "CD+_9") (pintype "passive"))
    )
    (net (code "86") (name "unconnected-(IC4-I1-Pad1)") (class "Default")
      (node (ref "IC4") (pin "1") (pinfunction "I1_1") (pintype "input"))
    )
    (net (code "87") (name "unconnected-(IC4-O1-Pad16)") (class "Default")
      (node (ref "IC4") (pin "16") (pinfunction "O1_16") (pintype "open_collector"))
    )
    (net (code "88") (name "unconnected-(IC5-CD+-Pad9)") (class "Default")
      (node (ref "IC5") (pin "9") (pinfunction "CD+_9") (pintype "passive"))
    )
    (net (code "89") (name "unconnected-(IC6-ADC7-Pad22)") (class "Default")
      (node (ref "IC6") (pin "22") (pinfunction "ADC7_22") (pintype "bidirectional"))
    )
    (net (code "90") (name "unconnected-(IC6-PC0(ADC0)-Pad23)") (class "Default")
      (node (ref "IC6") (pin "23") (pinfunction "PC0(ADC0)_23") (pintype "bidirectional"))
    )
    (net (code "91") (name "unconnected-(JP1-Pad6)") (class "Default")
      (node (ref "JP1") (pin "6") (pinfunction "6_6") (pintype "passive"))
    )
    (net (code "92") (name "unconnected-(JP1-Pad7)") (class "Default")
      (node (ref "JP1") (pin "7") (pinfunction "7_7") (pintype "passive"))
    )
    (net (code "93") (name "unconnected-(JP1-Pad8)") (class "Default")
      (node (ref "JP1") (pin "8") (pinfunction "8_8") (pintype "passive"))
    )
    (net (code "94") (name "unconnected-(RTC-Pad19)") (class "Default")
      (node (ref "RTC") (pin "19") (pinfunction "19_19") (pintype "passive"))
    )
  )
)
